# QwiicHUD_panel.net
KiCad netlist of a schematic drawn in EAGLE
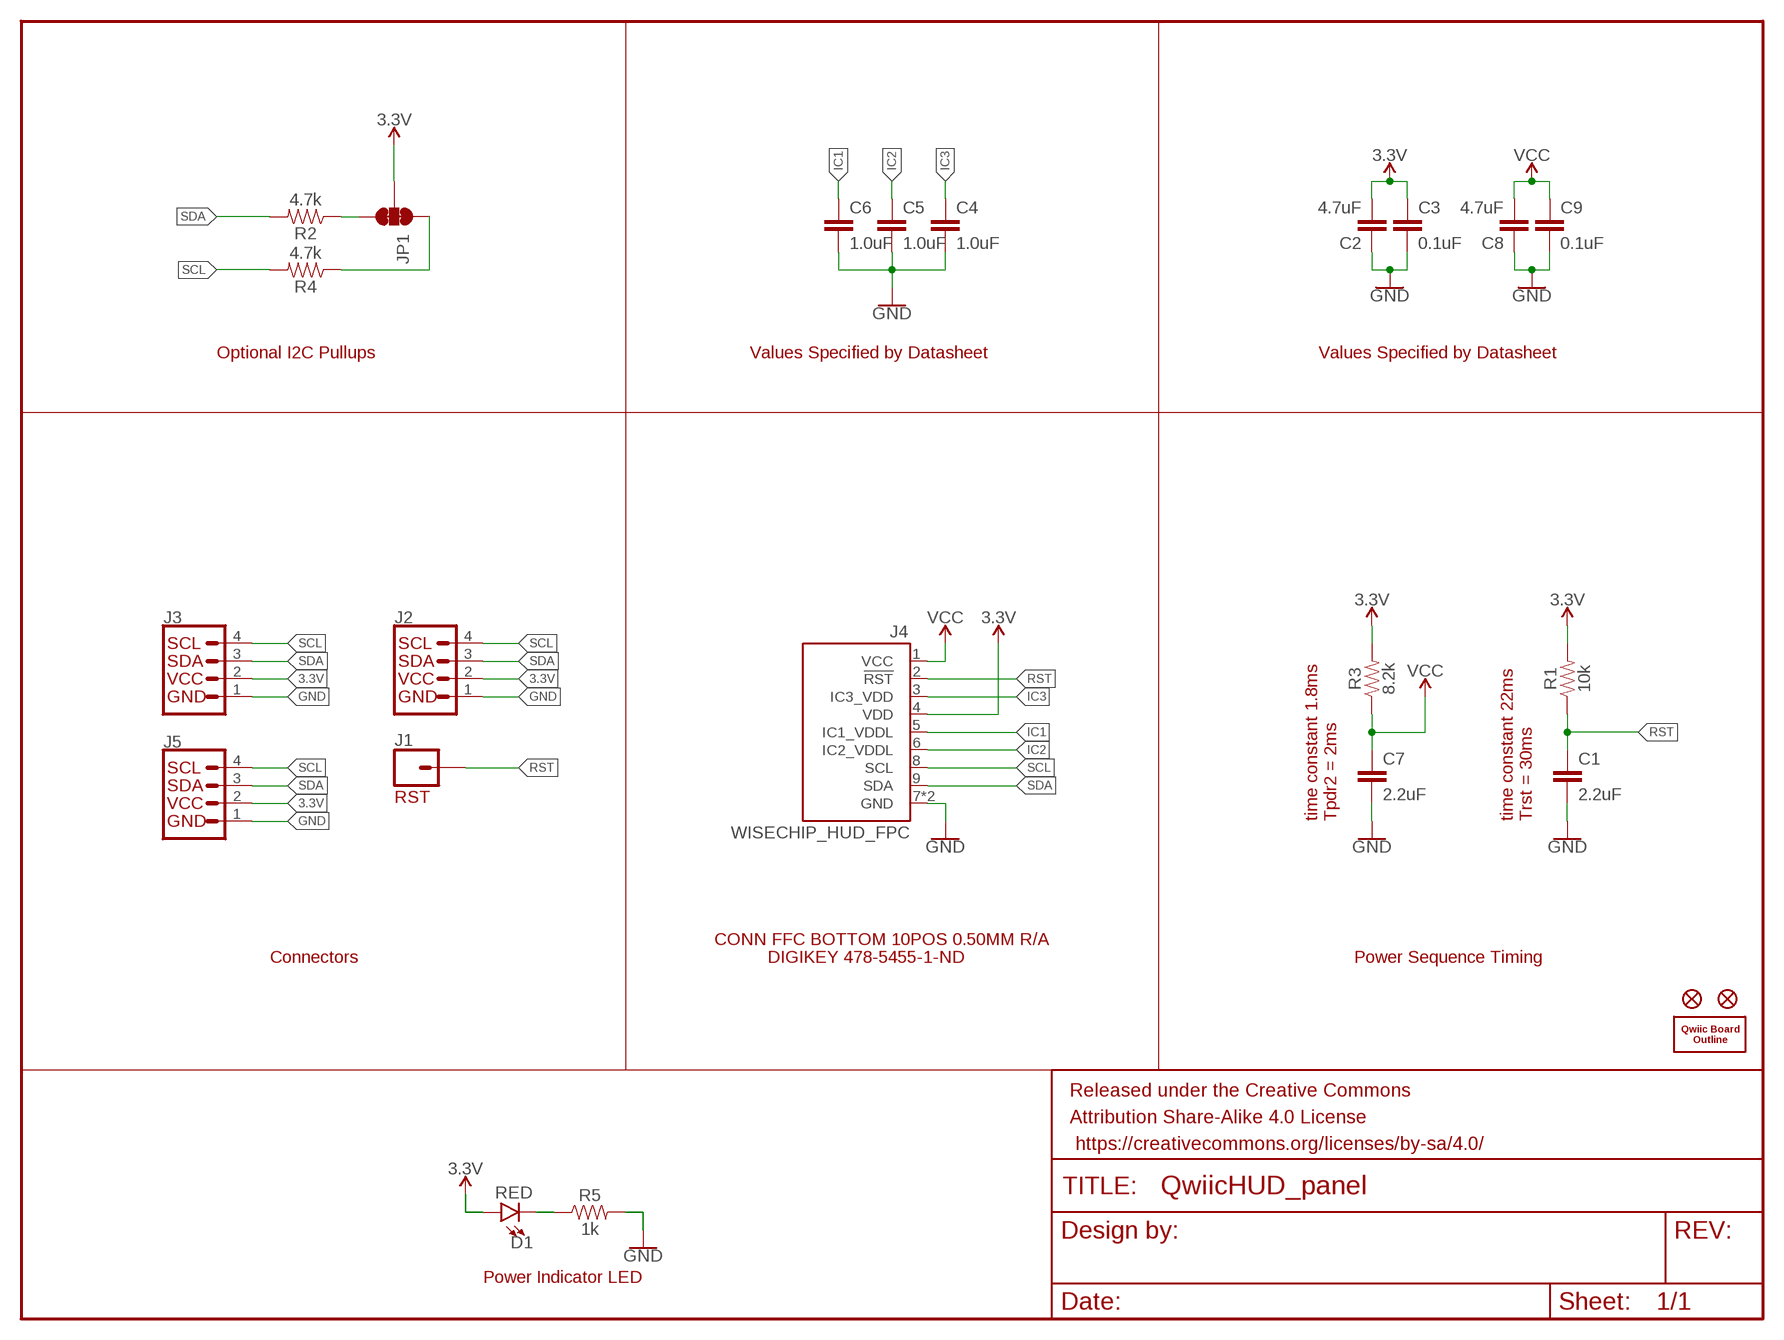
[diagram p0: schematic, sheet 1]

(export (version "E")
  (design (tool "Eeschema 10.0.6"))
  (components
    (comp (ref "C1")
      (value "2.2uF")
      (footprint "eagle-import:0603")
      (libsource (lib "eagle-import") (part "2.2UF-0603-10V-20%"))
    )
    (comp (ref "C2")
      (value "4.7uF")
      (footprint "eagle-import:0603")
      (libsource (lib "eagle-import") (part "4.7UF0603"))
    )
    (comp (ref "C3")
      (value "0.1uF")
      (footprint "eagle-import:0603")
      (libsource (lib "eagle-import") (part "0.1UF-0603-25V-5%"))
    )
    (comp (ref "C4")
      (value "1.0uF")
      (footprint "eagle-import:0603")
      (libsource (lib "eagle-import") (part "1.0UF-0603-16V-10%"))
    )
    (comp (ref "C5")
      (value "1.0uF")
      (footprint "eagle-import:0603")
      (libsource (lib "eagle-import") (part "1.0UF-0603-16V-10%"))
    )
    (comp (ref "C6")
      (value "1.0uF")
      (footprint "eagle-import:0603")
      (libsource (lib "eagle-import") (part "1.0UF-0603-16V-10%"))
    )
    (comp (ref "C7")
      (value "2.2uF")
      (footprint "eagle-import:0603")
      (libsource (lib "eagle-import") (part "2.2UF-0603-10V-20%"))
    )
    (comp (ref "C8")
      (value "4.7uF")
      (footprint "eagle-import:0603")
      (libsource (lib "eagle-import") (part "4.7UF0603"))
    )
    (comp (ref "C9")
      (value "0.1uF")
      (footprint "eagle-import:0603")
      (libsource (lib "eagle-import") (part "0.1UF-0603-25V-5%"))
    )
    (comp (ref "D1")
      (value "RED")
      (footprint "eagle-import:LED-0603")
      (libsource (lib "eagle-import") (part "LED-RED0603"))
    )
    (comp (ref "FD1")
      (value "FIDUCIALUFIDUCIAL")
      (footprint "eagle-import:FIDUCIAL-MICRO")
      (libsource (lib "eagle-import") (part "FIDUCIALUFIDUCIAL"))
    )
    (comp (ref "FD2")
      (value "FIDUCIALUFIDUCIAL")
      (footprint "eagle-import:FIDUCIAL-MICRO")
      (libsource (lib "eagle-import") (part "FIDUCIALUFIDUCIAL"))
    )
    (comp (ref "FRAME1")
      (value "FRAME-LETTER")
      (footprint "eagle-import:CREATIVE_COMMONS")
      (libsource (lib "eagle-import") (part "FRAME-LETTER"))
    )
    (comp (ref "J1")
      (value "CONN_01PTH_NO_SILK_YES_STOP")
      (footprint "eagle-import:1X01_NO_SILK")
      (libsource (lib "eagle-import") (part "CONN_01PTH_NO_SILK_YES_STOP"))
    )
    (comp (ref "J2")
      (value "I2C_STANDARD_NO_SILK")
      (footprint "eagle-import:1X04_NO_SILK")
      (libsource (lib "eagle-import") (part "I2C_STANDARD_NO_SILK"))
    )
    (comp (ref "J3")
      (value "I2C_STANDARDJS-1MM")
      (footprint "eagle-import:1X04_1MM_RA")
      (libsource (lib "eagle-import") (part "I2C_STANDARDJS-1MM"))
    )
    (comp (ref "J4")
      (value "WISECHIP_HUD_FPC")
      (footprint "eagle-import:SERIES6288")
      (libsource (lib "eagle-import") (part "WISECHIP_HUD_FPC"))
    )
    (comp (ref "J5")
      (value "I2C_STANDARDJS-1MM")
      (footprint "eagle-import:1X04_1MM_RA")
      (libsource (lib "eagle-import") (part "I2C_STANDARDJS-1MM"))
    )
    (comp (ref "JP1")
      (value "JUMPER-SMT_3_2-NC_TRACE_SILK")
      (footprint "eagle-import:SMT-JUMPER_3_2-NC_TRACE_SILK")
      (libsource (lib "eagle-import") (part "JUMPER-SMT_3_2-NC_TRACE_SILK"))
    )
    (comp (ref "R1")
      (value "10k")
      (footprint "eagle-import:0603")
      (libsource (lib "eagle-import") (part "10KOHM-0603-1/10W-1%"))
    )
    (comp (ref "R2")
      (value "4.7k")
      (footprint "eagle-import:0603")
      (libsource (lib "eagle-import") (part "4.7KOHM-0603-1/10W-1%"))
    )
    (comp (ref "R3")
      (value "8.2k")
      (footprint "eagle-import:0603")
      (libsource (lib "eagle-import") (part "8.2KOHM-0603-1/10W-5%"))
    )
    (comp (ref "R4")
      (value "4.7k")
      (footprint "eagle-import:0603")
      (libsource (lib "eagle-import") (part "4.7KOHM-0603-1/10W-1%"))
    )
    (comp (ref "R5")
      (value "1k")
      (footprint "eagle-import:0603")
      (libsource (lib "eagle-import") (part "1KOHM-0603-1/10W-1%"))
    )
    (comp (ref "U$2")
      (value "QWIIC_BOARD_OUTLINEH")
      (footprint "eagle-import:QWIIC_BOARD_MOUNT_HOLES")
      (libsource (lib "eagle-import") (part "QWIIC_BOARD_OUTLINEH"))
    )
  )
  (nets
    (net (code "1") (name "3.3V") (class "Default")
      (node (ref "C2") (pin "2") (pinfunction "2_2") (pintype "passive"))
      (node (ref "C3") (pin "1") (pinfunction "1_1") (pintype "passive"))
      (node (ref "D1") (pin "A") (pinfunction "A_A") (pintype "passive"))
      (node (ref "J2") (pin "2") (pinfunction "VCC_2") (pintype "power_in"))
      (node (ref "J3") (pin "2") (pinfunction "VCC_2") (pintype "power_in"))
      (node (ref "J4") (pin "4") (pinfunction "VDD_4") (pintype "bidirectional"))
      (node (ref "J5") (pin "2") (pinfunction "VCC_2") (pintype "power_in"))
      (node (ref "JP1") (pin "2") (pinfunction "2_2") (pintype "passive"))
      (node (ref "R1") (pin "2") (pinfunction "2_2") (pintype "passive"))
      (node (ref "R3") (pin "2") (pinfunction "2_2") (pintype "passive"))
    )
    (net (code "2") (name "GND") (class "Default")
      (node (ref "C1") (pin "2") (pinfunction "2_2") (pintype "passive"))
      (node (ref "C2") (pin "1") (pinfunction "1_1") (pintype "passive"))
      (node (ref "C3") (pin "2") (pinfunction "2_2") (pintype "passive"))
      (node (ref "C4") (pin "2") (pinfunction "2_2") (pintype "passive"))
      (node (ref "C5") (pin "2") (pinfunction "2_2") (pintype "passive"))
      (node (ref "C6") (pin "2") (pinfunction "2_2") (pintype "passive"))
      (node (ref "C7") (pin "2") (pinfunction "2_2") (pintype "passive"))
      (node (ref "C8") (pin "1") (pinfunction "1_1") (pintype "passive"))
      (node (ref "C9") (pin "2") (pinfunction "2_2") (pintype "passive"))
      (node (ref "J2") (pin "1") (pinfunction "GND_1") (pintype "power_in"))
      (node (ref "J3") (pin "1") (pinfunction "GND_1") (pintype "power_in"))
      (node (ref "J4") (pin "10") (pinfunction "GND_10") (pintype "bidirectional"))
      (node (ref "J4") (pin "7") (pinfunction "GND_7") (pintype "bidirectional"))
      (node (ref "J5") (pin "1") (pinfunction "GND_1") (pintype "power_in"))
      (node (ref "R5") (pin "2") (pinfunction "2_2") (pintype "passive"))
    )
    (net (code "3") (name "IC1") (class "Default")
      (node (ref "C6") (pin "1") (pinfunction "1_1") (pintype "passive"))
      (node (ref "J4") (pin "5") (pinfunction "IC1_VDDL_5") (pintype "bidirectional"))
    )
    (net (code "4") (name "IC2") (class "Default")
      (node (ref "C5") (pin "1") (pinfunction "1_1") (pintype "passive"))
      (node (ref "J4") (pin "6") (pinfunction "IC2_VDDL_6") (pintype "bidirectional"))
    )
    (net (code "5") (name "IC3") (class "Default")
      (node (ref "C4") (pin "1") (pinfunction "1_1") (pintype "passive"))
      (node (ref "J4") (pin "3") (pinfunction "IC3_VDD_3") (pintype "bidirectional"))
    )
    (net (code "6") (name "Net-(D1-PadC)") (class "Default")
      (node (ref "D1") (pin "C") (pinfunction "C_C") (pintype "passive"))
      (node (ref "R5") (pin "1") (pinfunction "1_1") (pintype "passive"))
    )
    (net (code "7") (name "Net-(JP1-Pad1)") (class "Default")
      (node (ref "JP1") (pin "1") (pinfunction "1_1") (pintype "passive"))
      (node (ref "R4") (pin "1") (pinfunction "1_1") (pintype "passive"))
    )
    (net (code "8") (name "Net-(JP1-Pad3)") (class "Default")
      (node (ref "JP1") (pin "3") (pinfunction "3_3") (pintype "passive"))
      (node (ref "R2") (pin "1") (pinfunction "1_1") (pintype "passive"))
    )
    (net (code "9") (name "RST") (class "Default")
      (node (ref "C1") (pin "1") (pinfunction "1_1") (pintype "passive"))
      (node (ref "J1") (pin "1") (pinfunction "1_1") (pintype "passive"))
      (node (ref "J4") (pin "2") (pinfunction "~{RST}_2") (pintype "bidirectional"))
      (node (ref "R1") (pin "1") (pinfunction "1_1") (pintype "passive"))
    )
    (net (code "10") (name "SCL") (class "Default")
      (node (ref "J2") (pin "4") (pinfunction "SCL_4") (pintype "passive"))
      (node (ref "J3") (pin "4") (pinfunction "SCL_4") (pintype "passive"))
      (node (ref "J4") (pin "8") (pinfunction "SCL_8") (pintype "bidirectional"))
      (node (ref "J5") (pin "4") (pinfunction "SCL_4") (pintype "passive"))
      (node (ref "R4") (pin "2") (pinfunction "2_2") (pintype "passive"))
    )
    (net (code "11") (name "SDA") (class "Default")
      (node (ref "J2") (pin "3") (pinfunction "SDA_3") (pintype "passive"))
      (node (ref "J3") (pin "3") (pinfunction "SDA_3") (pintype "passive"))
      (node (ref "J4") (pin "9") (pinfunction "SDA_9") (pintype "bidirectional"))
      (node (ref "J5") (pin "3") (pinfunction "SDA_3") (pintype "passive"))
      (node (ref "R2") (pin "2") (pinfunction "2_2") (pintype "passive"))
    )
    (net (code "12") (name "VCC") (class "Default")
      (node (ref "C7") (pin "1") (pinfunction "1_1") (pintype "passive"))
      (node (ref "C8") (pin "2") (pinfunction "2_2") (pintype "passive"))
      (node (ref "C9") (pin "1") (pinfunction "1_1") (pintype "passive"))
      (node (ref "J4") (pin "1") (pinfunction "VCC_1") (pintype "bidirectional"))
      (node (ref "R3") (pin "1") (pinfunction "1_1") (pintype "passive"))
    )
  )
)
